# TXPA.net
KiCad netlist of a schematic drawn in Altium Designer
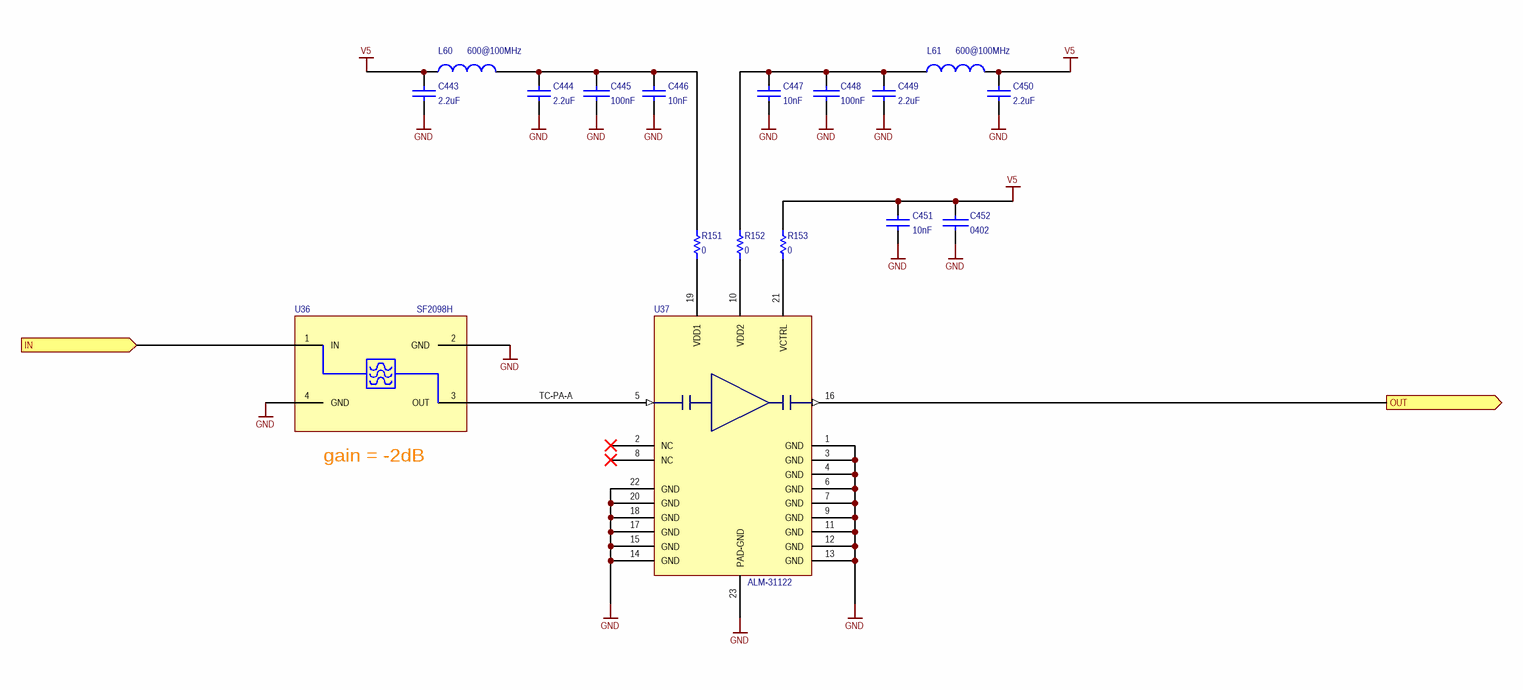
[diagram p0: TXPA.SchDoc]

(export (version "E")
  (design (tool "Eeschema 10.0.6"))
  (components
    (comp (ref "C443")
      (value "2.2uF")
      (footprint "generic:0805")
      (description "Ceramic Capacitor 2.2uF ±10% 10V X7R 0805")
      (fields (field (name "VOLTAGE") "10V") (field (name "MANUFACTURER") "Murata"))
      (libsource (lib "Graviton") (part "CAP 0805"))
    )
    (comp (ref "C444")
      (value "2.2uF")
      (footprint "generic:0805")
      (description "Ceramic Capacitor 2.2uF ±10% 10V X7R 0805")
      (fields (field (name "VOLTAGE") "10V") (field (name "MANUFACTURER") "Murata"))
      (libsource (lib "Graviton") (part "CAP 0805"))
    )
    (comp (ref "C445")
      (value "100nF")
      (footprint "generic:0402")
      (description "Ceramic Capacitor 100nF ±10% 16V X7R 0402")
      (fields (field (name "MANUFACTURER") "Murata") (field (name "VOLTAGE") "16V"))
      (libsource (lib "*") (part "CAP"))
    )
    (comp (ref "C446")
      (value "10nF")
      (footprint "generic:0402")
      (description "Ceramic Capacitor 10nF ±10% 25V X7R 0402")
      (fields (field (name "VOLTAGE") "25V") (field (name "MANUFACTURER") "Murata"))
      (libsource (lib "Graviton") (part "CAP 0402"))
    )
    (comp (ref "C447")
      (value "10nF")
      (footprint "generic:0402")
      (description "Ceramic Capacitor 10nF ±10% 25V X7R 0402")
      (fields (field (name "VOLTAGE") "25V") (field (name "MANUFACTURER") "Murata"))
      (libsource (lib "Graviton") (part "CAP 0402"))
    )
    (comp (ref "C448")
      (value "100nF")
      (footprint "generic:0402")
      (description "Ceramic Capacitor 100nF ±10% 16V X7R 0402")
      (fields (field (name "MANUFACTURER") "Murata") (field (name "VOLTAGE") "16V"))
      (libsource (lib "*") (part "CAP"))
    )
    (comp (ref "C449")
      (value "2.2uF")
      (footprint "generic:0805")
      (description "Ceramic Capacitor 2.2uF ±10% 10V X7R 0805")
      (fields (field (name "VOLTAGE") "10V") (field (name "MANUFACTURER") "Murata"))
      (libsource (lib "Graviton") (part "CAP 0805"))
    )
    (comp (ref "C450")
      (value "2.2uF")
      (footprint "generic:0805")
      (description "Ceramic Capacitor 2.2uF ±10% 10V X7R 0805")
      (fields (field (name "VOLTAGE") "10V") (field (name "MANUFACTURER") "Murata"))
      (libsource (lib "Graviton") (part "CAP 0805"))
    )
    (comp (ref "C451")
      (value "10nF")
      (footprint "generic:0402")
      (description "Ceramic Capacitor 10nF ±10% 25V X7R 0402")
      (fields (field (name "VOLTAGE") "25V") (field (name "MANUFACTURER") "Murata"))
      (libsource (lib "Graviton") (part "CAP 0402"))
    )
    (comp (ref "C452")
      (value "GRM155R71C104KA88J")
      (footprint "generic:0402")
      (description "Ceramic Capacitor 100nF ±10% 16V X7R 0402")
      (fields
        (field (name "MANUFACTURER") "Murata")
        (field (name "VOLTAGE") "16V")
        (field (name "PACKAGE") "0402")
      )
      (libsource (lib "*") (part "CAP"))
    )
    (comp (ref "L60")
      (value "600@100MHz")
      (footprint "0402")
      (description "Ferrite Bead 600-Ohm @ 100MHz 900mA 0402")
      (fields (field (name "MANUFACTURER") "Murata") (field (name "TOLERANCE") "±25%"))
      (libsource (lib "Graviton") (part "IND 0402"))
    )
    (comp (ref "L61")
      (value "600@100MHz")
      (footprint "0402")
      (description "Ferrite Bead 600-Ohm @ 100MHz 900mA 0402")
      (fields (field (name "MANUFACTURER") "Murata") (field (name "TOLERANCE") "±25%"))
      (libsource (lib "Graviton") (part "IND 0402"))
    )
    (comp (ref "R151")
      (value "0")
      (footprint "generic:0603")
      (description "Thick Film Resistor Jumper 0603")
      (fields (field (name "MANUFACTURER") "Panasonic") (field (name "Comment") "ERJ-3GEY0R00V"))
      (libsource (lib "Graviton") (part "RES 0603"))
    )
    (comp (ref "R152")
      (value "0")
      (footprint "generic:0603")
      (description "Thick Film Resistor Jumper 0603")
      (fields (field (name "MANUFACTURER") "Panasonic") (field (name "Comment") "ERJ-3GEY0R00V"))
      (libsource (lib "Graviton") (part "RES 0603"))
    )
    (comp (ref "R153")
      (value "0")
      (footprint "generic:0603")
      (description "Thick Film Resistor Jumper 0603")
      (fields (field (name "MANUFACTURER") "Panasonic") (field (name "Comment") "ERJ-3GEY0R00V"))
      (libsource (lib "Graviton") (part "RES 0603"))
    )
    (comp (ref "U36")
      (value "SF2098H")
      (footprint "rfm:SM2016-4")
      (description "915 MHz SAW Filter")
      (fields (field (name "MANUFACTURER") "RFM"))
      (libsource (lib "rfm") (part "SF2098H"))
    )
    (comp (ref "U37")
      (value "ALM-31122")
      (footprint "ALM-31122")
      (description "1-watt High-Linearity Power Amplifier")
      (fields (field (name "MANUFACTURER") "Avago"))
      (libsource (lib "avago") (part "ALM-31122"))
    )
  )
  (nets
    (net (code "1") (name "/IN") (class "Default")
      (node (ref "U36") (pin "1") (pinfunction "IN_1") (pintype "passive"))
    )
    (net (code "2") (name "/OUT") (class "Default")
      (node (ref "U37") (pin "16") (pinfunction "RFOUT_16") (pintype "output"))
    )
    (net (code "3") (name "/TC-PA-A") (class "Default")
      (node (ref "U36") (pin "3") (pinfunction "OUT_3") (pintype "passive"))
      (node (ref "U37") (pin "5") (pinfunction "RFIN_5") (pintype "input"))
    )
    (net (code "4") (name "GND") (class "Default")
      (node (ref "C443") (pin "1") (pinfunction "1_1") (pintype "passive"))
      (node (ref "C444") (pin "1") (pinfunction "1_1") (pintype "passive"))
      (node (ref "C445") (pin "1") (pinfunction "1_1") (pintype "passive"))
      (node (ref "C446") (pin "1") (pinfunction "1_1") (pintype "passive"))
      (node (ref "C447") (pin "1") (pinfunction "1_1") (pintype "passive"))
      (node (ref "C448") (pin "1") (pinfunction "1_1") (pintype "passive"))
      (node (ref "C449") (pin "1") (pinfunction "1_1") (pintype "passive"))
      (node (ref "C450") (pin "1") (pinfunction "1_1") (pintype "passive"))
      (node (ref "C451") (pin "1") (pinfunction "1_1") (pintype "passive"))
      (node (ref "C452") (pin "1") (pinfunction "1_1") (pintype "passive"))
      (node (ref "U36") (pin "2") (pinfunction "GND_2") (pintype "passive"))
      (node (ref "U36") (pin "4") (pinfunction "GND_4") (pintype "passive"))
      (node (ref "U37") (pin "1") (pinfunction "GND_1") (pintype "passive"))
      (node (ref "U37") (pin "11") (pinfunction "GND_11") (pintype "passive"))
      (node (ref "U37") (pin "12") (pinfunction "GND_12") (pintype "passive"))
      (node (ref "U37") (pin "13") (pinfunction "GND_13") (pintype "passive"))
      (node (ref "U37") (pin "14") (pinfunction "GND_14") (pintype "passive"))
      (node (ref "U37") (pin "15") (pinfunction "GND_15") (pintype "passive"))
      (node (ref "U37") (pin "17") (pinfunction "GND_17") (pintype "passive"))
      (node (ref "U37") (pin "18") (pinfunction "GND_18") (pintype "passive"))
      (node (ref "U37") (pin "20") (pinfunction "GND_20") (pintype "passive"))
      (node (ref "U37") (pin "22") (pinfunction "GND_22") (pintype "passive"))
      (node (ref "U37") (pin "23") (pinfunction "PAD-GND_23") (pintype "passive"))
      (node (ref "U37") (pin "3") (pinfunction "GND_3") (pintype "passive"))
      (node (ref "U37") (pin "4") (pinfunction "GND_4") (pintype "passive"))
      (node (ref "U37") (pin "6") (pinfunction "GND_6") (pintype "passive"))
      (node (ref "U37") (pin "7") (pinfunction "GND_7") (pintype "passive"))
      (node (ref "U37") (pin "9") (pinfunction "GND_9") (pintype "passive"))
    )
    (net (code "5") (name "Net-(C444-Pad2)") (class "Default")
      (node (ref "C444") (pin "2") (pinfunction "2_2") (pintype "passive"))
      (node (ref "C445") (pin "2") (pinfunction "2_2") (pintype "passive"))
      (node (ref "C446") (pin "2") (pinfunction "2_2") (pintype "passive"))
      (node (ref "L60") (pin "1") (pinfunction "1_1") (pintype "passive"))
      (node (ref "R151") (pin "2") (pinfunction "2_2") (pintype "passive"))
    )
    (net (code "6") (name "Net-(C447-Pad2)") (class "Default")
      (node (ref "C447") (pin "2") (pinfunction "2_2") (pintype "passive"))
      (node (ref "C448") (pin "2") (pinfunction "2_2") (pintype "passive"))
      (node (ref "C449") (pin "2") (pinfunction "2_2") (pintype "passive"))
      (node (ref "L61") (pin "2") (pinfunction "2_2") (pintype "passive"))
      (node (ref "R152") (pin "2") (pinfunction "2_2") (pintype "passive"))
    )
    (net (code "7") (name "Net-(U37-VCTRL)") (class "Default")
      (node (ref "R153") (pin "1") (pinfunction "1_1") (pintype "passive"))
      (node (ref "U37") (pin "21") (pinfunction "VCTRL_21") (pintype "passive"))
    )
    (net (code "8") (name "Net-(U37-VDD1)") (class "Default")
      (node (ref "R151") (pin "1") (pinfunction "1_1") (pintype "passive"))
      (node (ref "U37") (pin "19") (pinfunction "VDD1_19") (pintype "passive"))
    )
    (net (code "9") (name "Net-(U37-VDD2)") (class "Default")
      (node (ref "R152") (pin "1") (pinfunction "1_1") (pintype "passive"))
      (node (ref "U37") (pin "10") (pinfunction "VDD2_10") (pintype "passive"))
    )
    (net (code "10") (name "V5") (class "Default")
      (node (ref "C443") (pin "2") (pinfunction "2_2") (pintype "passive"))
      (node (ref "C450") (pin "2") (pinfunction "2_2") (pintype "passive"))
      (node (ref "C451") (pin "2") (pinfunction "2_2") (pintype "passive"))
      (node (ref "C452") (pin "2") (pinfunction "2_2") (pintype "passive"))
      (node (ref "L60") (pin "2") (pinfunction "2_2") (pintype "passive"))
      (node (ref "L61") (pin "1") (pinfunction "1_1") (pintype "passive"))
      (node (ref "R153") (pin "2") (pinfunction "2_2") (pintype "passive"))
    )
    (net (code "11") (name "unconnected-(U37-NC-Pad2)") (class "Default")
      (node (ref "U37") (pin "2") (pinfunction "NC_2") (pintype "passive+no_connect"))
    )
    (net (code "12") (name "unconnected-(U37-NC-Pad8)") (class "Default")
      (node (ref "U37") (pin "8") (pinfunction "NC_8") (pintype "passive+no_connect"))
    )
  )
)
